# Stereo_master_section.net
KiCad netlist of a schematic drawn in EAGLE
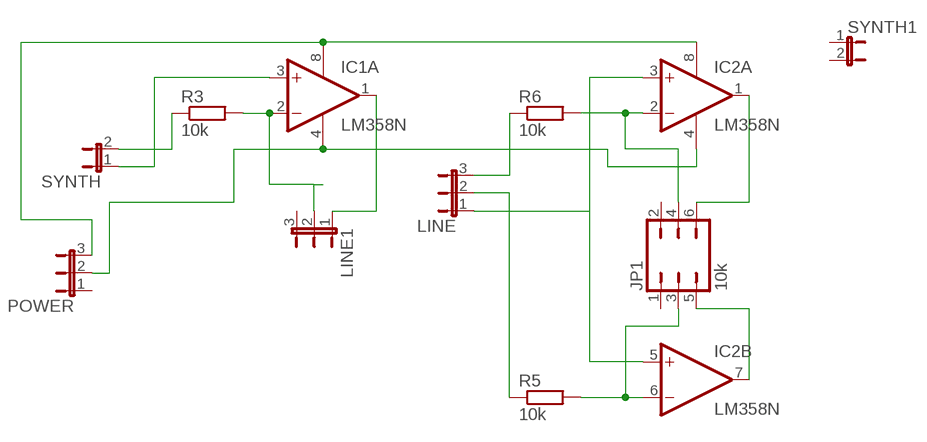
[diagram p0: schematic, sheet 1]

(export (version "E")
  (design (tool "Eeschema 10.0.6"))
  (components
    (comp (ref "IC1")
      (value "LM358N")
      (footprint "eagle-import:DIL08")
      (libsource (lib "eagle-import") (part "LM358N"))
    )
    (comp (ref "IC2")
      (value "LM358N")
      (footprint "eagle-import:DIL08")
      (libsource (lib "eagle-import") (part "LM358N"))
    )
    (comp (ref "JP1")
      (value "10k")
      (footprint "eagle-import:JP3Q")
      (libsource (lib "eagle-import") (part "JP3Q"))
    )
    (comp (ref "LINE")
      (value "JP2E")
      (footprint "eagle-import:JP2")
      (libsource (lib "eagle-import") (part "JP2E"))
    )
    (comp (ref "LINE1")
      (value "JP2E")
      (footprint "eagle-import:JP2")
      (libsource (lib "eagle-import") (part "JP2E"))
    )
    (comp (ref "POWER")
      (value "JP2E")
      (footprint "eagle-import:JP2")
      (libsource (lib "eagle-import") (part "JP2E"))
    )
    (comp (ref "R3")
      (value "10k")
      (footprint "eagle-import:0207_7")
      (libsource (lib "eagle-import") (part "R-EU_0207/7"))
    )
    (comp (ref "R5")
      (value "10k")
      (footprint "eagle-import:0207_7")
      (libsource (lib "eagle-import") (part "R-EU_0207/7"))
    )
    (comp (ref "R6")
      (value "10k")
      (footprint "eagle-import:0207_7")
      (libsource (lib "eagle-import") (part "R-EU_0207/7"))
    )
    (comp (ref "SYNTH")
      (value "JP1E")
      (footprint "eagle-import:JP1")
      (libsource (lib "eagle-import") (part "JP1E"))
    )
    (comp (ref "SYNTH1")
      (value "JP1E")
      (footprint "eagle-import:JP1")
      (libsource (lib "eagle-import") (part "JP1E"))
    )
  )
  (nets
    (net (code "1") (name "Net-(IC1A-+IN)") (class "Default")
      (node (ref "IC1") (pin "3") (pinfunction "+IN_3") (pintype "input"))
      (node (ref "SYNTH") (pin "1") (pinfunction "1_1") (pintype "passive"))
    )
    (net (code "2") (name "Net-(IC1A--IN)") (class "Default")
      (node (ref "IC1") (pin "2") (pinfunction "-IN_2") (pintype "input"))
      (node (ref "LINE1") (pin "2") (pinfunction "2_2") (pintype "passive"))
      (node (ref "R3") (pin "2") (pinfunction "2_2") (pintype "passive"))
    )
    (net (code "3") (name "Net-(IC1A-OUT)") (class "Default")
      (node (ref "IC1") (pin "1") (pinfunction "OUT_1") (pintype "output"))
      (node (ref "LINE1") (pin "1") (pinfunction "1_1") (pintype "passive"))
    )
    (net (code "4") (name "Net-(IC1C-V+)") (class "Default")
      (node (ref "IC1") (pin "8") (pinfunction "V+_8") (pintype "power_in"))
      (node (ref "IC2") (pin "8") (pinfunction "V+_8") (pintype "power_in"))
      (node (ref "POWER") (pin "3") (pinfunction "3_3") (pintype "passive"))
    )
    (net (code "5") (name "Net-(IC1C-V-)") (class "Default")
      (node (ref "IC1") (pin "4") (pinfunction "V-_4") (pintype "power_in"))
      (node (ref "IC2") (pin "4") (pinfunction "V-_4") (pintype "power_in"))
      (node (ref "POWER") (pin "2") (pinfunction "2_2") (pintype "passive"))
    )
    (net (code "6") (name "Net-(IC2A-+IN)") (class "Default")
      (node (ref "IC2") (pin "3") (pinfunction "+IN_3") (pintype "input"))
      (node (ref "IC2") (pin "5") (pinfunction "+IN_5") (pintype "input"))
    )
    (net (code "7") (name "Net-(IC2A--IN)") (class "Default")
      (node (ref "IC2") (pin "2") (pinfunction "-IN_2") (pintype "input"))
      (node (ref "JP1") (pin "4") (pinfunction "4_4") (pintype "passive"))
      (node (ref "R6") (pin "2") (pinfunction "2_2") (pintype "passive"))
    )
    (net (code "8") (name "Net-(IC2A-OUT)") (class "Default")
      (node (ref "IC2") (pin "1") (pinfunction "OUT_1") (pintype "output"))
      (node (ref "JP1") (pin "6") (pinfunction "6_6") (pintype "passive"))
    )
    (net (code "9") (name "Net-(IC2B--IN)") (class "Default")
      (node (ref "IC2") (pin "6") (pinfunction "-IN_6") (pintype "input"))
      (node (ref "JP1") (pin "3") (pinfunction "3_3") (pintype "passive"))
      (node (ref "R5") (pin "2") (pinfunction "2_2") (pintype "passive"))
    )
    (net (code "10") (name "Net-(IC2B-OUT)") (class "Default")
      (node (ref "IC2") (pin "7") (pinfunction "OUT_7") (pintype "output"))
      (node (ref "JP1") (pin "5") (pinfunction "5_5") (pintype "passive"))
    )
    (net (code "11") (name "Net-(LINE-Pad2)") (class "Default")
      (node (ref "LINE") (pin "2") (pinfunction "2_2") (pintype "passive"))
      (node (ref "R5") (pin "1") (pinfunction "1_1") (pintype "passive"))
    )
    (net (code "12") (name "Net-(LINE-Pad3)") (class "Default")
      (node (ref "LINE") (pin "3") (pinfunction "3_3") (pintype "passive"))
      (node (ref "R6") (pin "1") (pinfunction "1_1") (pintype "passive"))
    )
    (net (code "13") (name "Net-(R3-Pad1)") (class "Default")
      (node (ref "R3") (pin "1") (pinfunction "1_1") (pintype "passive"))
      (node (ref "SYNTH") (pin "2") (pinfunction "2_2") (pintype "passive"))
    )
    (net (code "14") (name "unconnected-(JP1-Pad1)") (class "Default")
      (node (ref "JP1") (pin "1") (pinfunction "1_1") (pintype "passive"))
    )
    (net (code "15") (name "unconnected-(JP1-Pad2)") (class "Default")
      (node (ref "JP1") (pin "2") (pinfunction "2_2") (pintype "passive"))
    )
    (net (code "16") (name "unconnected-(LINE-Pad1)") (class "Default")
      (node (ref "LINE") (pin "1") (pinfunction "1_1") (pintype "passive"))
    )
    (net (code "17") (name "unconnected-(LINE1-Pad3)") (class "Default")
      (node (ref "LINE1") (pin "3") (pinfunction "3_3") (pintype "passive"))
    )
    (net (code "18") (name "unconnected-(POWER-Pad1)") (class "Default")
      (node (ref "POWER") (pin "1") (pinfunction "1_1") (pintype "passive"))
    )
    (net (code "19") (name "unconnected-(SYNTH1-Pad1)") (class "Default")
      (node (ref "SYNTH1") (pin "1") (pinfunction "1_1") (pintype "passive"))
    )
    (net (code "20") (name "unconnected-(SYNTH1-Pad2)") (class "Default")
      (node (ref "SYNTH1") (pin "2") (pinfunction "2_2") (pintype "passive"))
    )
  )
)
